# untitled.net
KiCad netlist of a schematic drawn in EAGLE
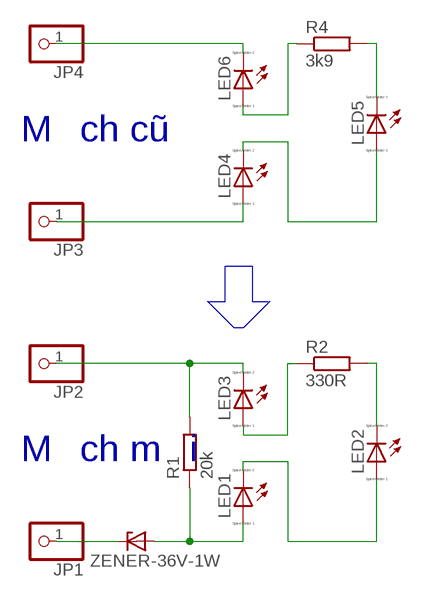
[diagram p0: schematic, sheet 1]

(export (version "E")
  (design (tool "Eeschema 10.0.6"))
  (components
    (comp (ref "JP1")
      (value "PINHD-1X1")
      (footprint "eagle-import:1X01")
      (libsource (lib "eagle-import") (part "PINHD-1X1"))
    )
    (comp (ref "JP2")
      (value "PINHD-1X1")
      (footprint "eagle-import:1X01")
      (libsource (lib "eagle-import") (part "PINHD-1X1"))
    )
    (comp (ref "JP3")
      (value "PINHD-1X1")
      (footprint "eagle-import:1X01")
      (libsource (lib "eagle-import") (part "PINHD-1X1"))
    )
    (comp (ref "JP4")
      (value "PINHD-1X1")
      (footprint "eagle-import:1X01")
      (libsource (lib "eagle-import") (part "PINHD-1X1"))
    )
    (comp (ref "LED1")
      (value "LED_E")
      (footprint "eagle-import:LED_1206")
      (libsource (lib "eagle-import") (part "LED_E"))
    )
    (comp (ref "LED2")
      (value "LED_E")
      (footprint "eagle-import:LED_1206")
      (libsource (lib "eagle-import") (part "LED_E"))
    )
    (comp (ref "LED3")
      (value "LED_E")
      (footprint "eagle-import:LED_1206")
      (libsource (lib "eagle-import") (part "LED_E"))
    )
    (comp (ref "LED4")
      (value "LED_E")
      (footprint "eagle-import:LED_1206")
      (libsource (lib "eagle-import") (part "LED_E"))
    )
    (comp (ref "LED5")
      (value "LED_E")
      (footprint "eagle-import:LED_1206")
      (libsource (lib "eagle-import") (part "LED_E"))
    )
    (comp (ref "LED6")
      (value "LED_E")
      (footprint "eagle-import:LED_1206")
      (libsource (lib "eagle-import") (part "LED_E"))
    )
    (comp (ref "R1")
      (value "20k")
      (footprint "eagle-import:0204_7")
      (libsource (lib "eagle-import") (part "R-EU_0204/7"))
    )
    (comp (ref "R2")
      (value "330R")
      (footprint "eagle-import:0204_7")
      (libsource (lib "eagle-import") (part "R-EU_0204/7"))
    )
    (comp (ref "R4")
      (value "3k9")
      (footprint "eagle-import:0204_7")
      (libsource (lib "eagle-import") (part "R-EU_0204/7"))
    )
    (comp (ref "ZENER-36V-1W")
      (value "1N4728")
      (footprint "eagle-import:DO41Z10")
      (libsource (lib "eagle-import") (part "1N4728"))
    )
  )
  (nets
    (net (code "1") (name "Net-(JP1-Pad1)") (class "Default")
      (node (ref "JP1") (pin "1") (pinfunction "1_1") (pintype "passive"))
      (node (ref "ZENER-36V-1W") (pin "C") (pinfunction "C_C") (pintype "passive"))
    )
    (net (code "2") (name "Net-(JP2-Pad1)") (class "Default")
      (node (ref "JP2") (pin "1") (pinfunction "1_1") (pintype "passive"))
      (node (ref "LED3") (pin "C") (pinfunction "C_C") (pintype "passive"))
      (node (ref "R1") (pin "2") (pinfunction "2_2") (pintype "passive"))
    )
    (net (code "3") (name "Net-(JP3-Pad1)") (class "Default")
      (node (ref "JP3") (pin "1") (pinfunction "1_1") (pintype "passive"))
      (node (ref "LED4") (pin "A") (pinfunction "A_A") (pintype "passive"))
    )
    (net (code "4") (name "Net-(JP4-Pad1)") (class "Default")
      (node (ref "JP4") (pin "1") (pinfunction "1_1") (pintype "passive"))
      (node (ref "LED6") (pin "C") (pinfunction "C_C") (pintype "passive"))
    )
    (net (code "5") (name "Net-(LED1-PadA)") (class "Default")
      (node (ref "LED1") (pin "A") (pinfunction "A_A") (pintype "passive"))
      (node (ref "R1") (pin "1") (pinfunction "1_1") (pintype "passive"))
      (node (ref "ZENER-36V-1W") (pin "A") (pinfunction "A_A") (pintype "passive"))
    )
    (net (code "6") (name "Net-(LED1-PadC)") (class "Default")
      (node (ref "LED1") (pin "C") (pinfunction "C_C") (pintype "passive"))
      (node (ref "LED2") (pin "A") (pinfunction "A_A") (pintype "passive"))
    )
    (net (code "7") (name "Net-(LED2-PadC)") (class "Default")
      (node (ref "LED2") (pin "C") (pinfunction "C_C") (pintype "passive"))
      (node (ref "R2") (pin "2") (pinfunction "2_2") (pintype "passive"))
    )
    (net (code "8") (name "Net-(LED3-PadA)") (class "Default")
      (node (ref "LED3") (pin "A") (pinfunction "A_A") (pintype "passive"))
      (node (ref "R2") (pin "1") (pinfunction "1_1") (pintype "passive"))
    )
    (net (code "9") (name "Net-(LED4-PadC)") (class "Default")
      (node (ref "LED4") (pin "C") (pinfunction "C_C") (pintype "passive"))
      (node (ref "LED5") (pin "A") (pinfunction "A_A") (pintype "passive"))
    )
    (net (code "10") (name "Net-(LED5-PadC)") (class "Default")
      (node (ref "LED5") (pin "C") (pinfunction "C_C") (pintype "passive"))
      (node (ref "R4") (pin "2") (pinfunction "2_2") (pintype "passive"))
    )
    (net (code "11") (name "Net-(LED6-PadA)") (class "Default")
      (node (ref "LED6") (pin "A") (pinfunction "A_A") (pintype "passive"))
      (node (ref "R4") (pin "1") (pinfunction "1_1") (pintype "passive"))
    )
  )
)
